# DriverBoardForCNC.net
KiCad netlist of a schematic drawn in Altium Designer
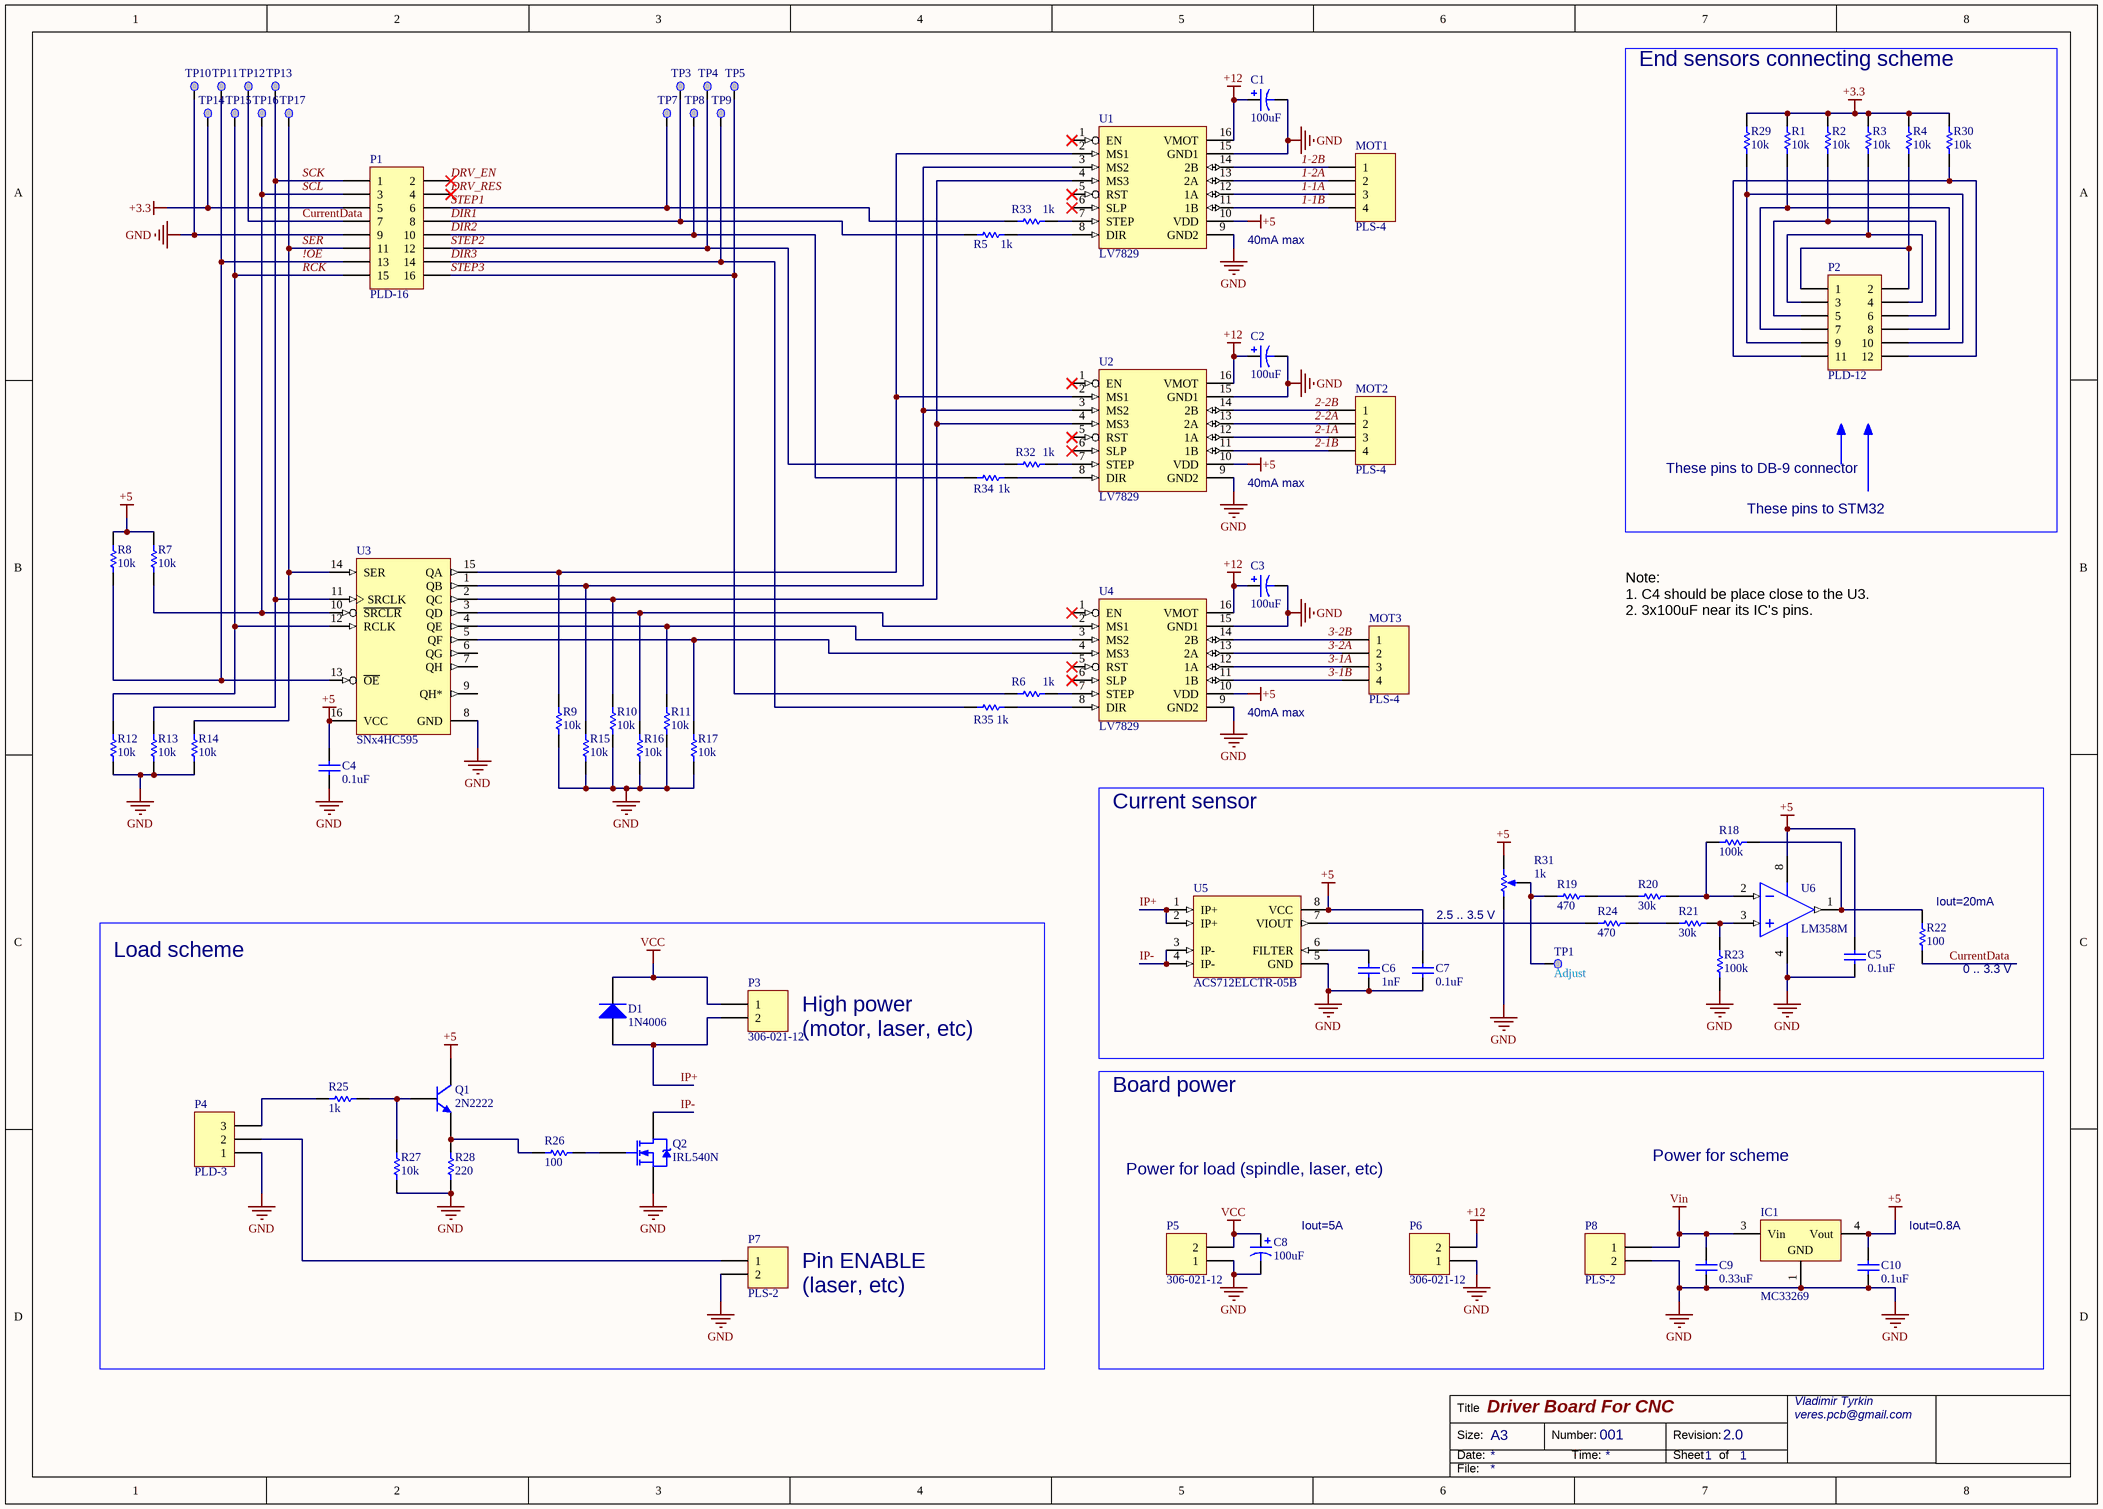
[diagram p0: DriverBoardForCNC.SchDoc]

(export (version "E")
  (design (tool "Eeschema 10.0.6"))
  (components
    (comp (ref "C1")
      (value "100uF")
      (footprint "UD-6,3X5,8_NICHICON")
      (description "Polarized Capacitor (Radial) 16V, 105°C, 20% 6.3x5.4mm")
      (fields (field (name "MANUFACTURER") "JB") (field (name "MANUFACTURER_PART_NUMBER") "JCL1C101M063054"))
      (libsource (lib "DriverBoardForCNC") (part "Cap Pol1"))
    )
    (comp (ref "C2")
      (value "100uF")
      (footprint "UD-6,3X5,8_NICHICON")
      (description "Polarized Capacitor (Radial) 16V, 105°C, 20% 6.3x5.4mm")
      (fields (field (name "MANUFACTURER") "JB") (field (name "MANUFACTURER_PART_NUMBER") "JCL1C101M063054"))
      (libsource (lib "DriverBoardForCNC") (part "Cap Pol1"))
    )
    (comp (ref "C3")
      (value "100uF")
      (footprint "UD-6,3X5,8_NICHICON")
      (description "Polarized Capacitor (Radial) 16V, 105°C, 20% 6.3x5.4mm")
      (fields (field (name "MANUFACTURER") "JB") (field (name "MANUFACTURER_PART_NUMBER") "JCL1C101M063054"))
      (libsource (lib "DriverBoardForCNC") (part "Cap Pol1"))
    )
    (comp (ref "C4")
      (value "0.1uF")
      (footprint "C1206")
      (description "Capacitor ceramic SMD")
      (fields
        (field (name "MANUFACTURER") "Murata")
        (field (name "MANUFACTURER_PART_NUMBER") "GRM319R71H104K")
      )
      (libsource (lib "DriverBoardForCNC") (part "Cap"))
    )
    (comp (ref "C5")
      (value "0.1uF")
      (footprint "C1206")
      (description "Capacitor ceramic SMD")
      (fields
        (field (name "MANUFACTURER") "Murata")
        (field (name "MANUFACTURER_PART_NUMBER") "GRM319R71H104K")
      )
      (libsource (lib "DriverBoardForCNC") (part "Cap"))
    )
    (comp (ref "C6")
      (value "1nF")
      (footprint "C0805")
      (description "Capacitor ceramic SMD")
      (fields
        (field (name "MANUFACTURER") "HOLYSTONECAPS")
        (field (name "MANUFACTURER_PART_NUMBER") "MLCC1000pFX7R50V10%0805")
      )
      (libsource (lib "DriverBoardForCNC") (part "Cap"))
    )
    (comp (ref "C7")
      (value "0.1uF")
      (footprint "C1206")
      (description "Capacitor ceramic SMD")
      (fields
        (field (name "MANUFACTURER") "Murata")
        (field (name "MANUFACTURER_PART_NUMBER") "GRM319R71H104K")
      )
      (libsource (lib "DriverBoardForCNC") (part "Cap"))
    )
    (comp (ref "C8")
      (value "100uF")
      (footprint "UD-6,3X5,8_NICHICON")
      (description "Polarized Capacitor (Radial) 16V, 105°C, 20% 6.3x5.4mm")
      (fields (field (name "MANUFACTURER") "JB") (field (name "MANUFACTURER_PART_NUMBER") "JCL1C101M063054"))
      (libsource (lib "DriverBoardForCNC") (part "Cap Pol1"))
    )
    (comp (ref "C9")
      (value "0.33uF")
      (footprint "C1206")
      (description "Capacitor ceramic SMD")
      (fields
        (field (name "MANUFACTURER") "Murata")
        (field (name "MANUFACTURER_PART_NUMBER") "GRM319R71H334KA01D")
      )
      (libsource (lib "DriverBoardForCNC") (part "Cap"))
    )
    (comp (ref "C10")
      (value "0.1uF")
      (footprint "C1206")
      (description "Capacitor ceramic SMD")
      (fields
        (field (name "MANUFACTURER") "Murata")
        (field (name "MANUFACTURER_PART_NUMBER") "GRM319R71H104K")
      )
      (libsource (lib "DriverBoardForCNC") (part "Cap"))
    )
    (comp (ref "D1")
      (value "1N4006")
      (footprint "DO-41")
      (description "1 Amp General Purpose Rectifier")
      (fields (field (name "MANUFACTURER") "DC COMPONENTS CO., LTD."))
      (libsource (lib "DriverBoardForCNC") (part "Diode 1N4004"))
    )
    (comp (ref "IC1")
      (value "MC33269")
      (footprint "DPAK")
      (description "5V Voltage Regulator")
      (fields
        (field (name "MANUFACTURER_PART_NUMBER") "MC33269DT−5.0")
        (field (name "MANUFACTURER") "ON Semiconductor")
      )
      (libsource (lib "DriverBoardForCNC") (part "Volt Reg 5V"))
    )
    (comp (ref "MOT1")
      (value "PLS-4")
      (footprint "HDR1X4")
      (description "Header, 4-Pin")
      (fields
        (field (name "MANUFACTURER") "Connfly")
        (field (name "MANUFACTURER_PART_NUMBER") "DS1021-1*4SF11-B")
      )
      (libsource (lib "DriverBoardForCNC") (part "Header 4"))
    )
    (comp (ref "MOT2")
      (value "PLS-4")
      (footprint "HDR1X4")
      (description "Header, 4-Pin")
      (fields
        (field (name "MANUFACTURER") "Connfly")
        (field (name "MANUFACTURER_PART_NUMBER") "DS1021-1*4SF11-B")
      )
      (libsource (lib "DriverBoardForCNC") (part "Header 4"))
    )
    (comp (ref "MOT3")
      (value "PLS-4")
      (footprint "HDR1X4")
      (description "Header, 4-Pin")
      (fields
        (field (name "MANUFACTURER") "Connfly")
        (field (name "MANUFACTURER_PART_NUMBER") "DS1021-1*4SF11-B")
      )
      (libsource (lib "DriverBoardForCNC") (part "Header 4"))
    )
    (comp (ref "P1")
      (value "PLD-16")
      (footprint "HDR2X8")
      (description "Header, 8-Pin, Dual row")
      (fields
        (field (name "MANUFACTURER") "Connfly")
        (field (name "MANUFACTURER_PART_NUMBER") "DS1021-2*8SF11-B")
      )
      (libsource (lib "DriverBoardForCNC") (part "Header 8X2"))
    )
    (comp (ref "P2")
      (value "PLD-12")
      (footprint "HDR2X6")
      (description "Header, 6-Pin, Dual row")
      (fields
        (field (name "MANUFACTURER") "Connfly")
        (field (name "MANUFACTURER_PART_NUMBER") "DS1021-2*6SF11-B")
      )
      (libsource (lib "DriverBoardForCNC") (part "Header 6X2"))
    )
    (comp (ref "P3")
      (value "306-021-12")
      (footprint "W237-102")
      (description "Screw connector, 2-Pin")
      (fields
        (field (name "MANUFACTURER") "Ningbo Xinya M&E")
        (field (name "MANUFACTURER_PART_NUMBER") "XY306A-5.0-2P-12")
      )
      (libsource (lib "") (part "Header 2_1"))
    )
    (comp (ref "P4")
      (value "PLD-3")
      (footprint "HDR1X3")
      (description "Header, 3-Pin")
      (fields
        (field (name "MANUFACTURER") "Connfly")
        (field (name "MANUFACTURER_PART_NUMBER") "DS1021-1*3SF11-B")
      )
      (libsource (lib "DriverBoardForCNC") (part "Header 3"))
    )
    (comp (ref "P5")
      (value "306-021-12")
      (footprint "W237-102")
      (description "Screw connector, 2-Pin")
      (fields
        (field (name "MANUFACTURER") "Ningbo Xinya M&E")
        (field (name "MANUFACTURER_PART_NUMBER") "XY306A-5.0-2P-12")
      )
      (libsource (lib "DriverBoardForCNC") (part "Header 2"))
    )
    (comp (ref "P6")
      (value "306-021-12")
      (footprint "W237-102")
      (description "Screw connector, 2-Pin")
      (fields
        (field (name "MANUFACTURER") "Ningbo Xinya M&E")
        (field (name "MANUFACTURER_PART_NUMBER") "XY306A-5.0-2P-12")
      )
      (libsource (lib "DriverBoardForCNC") (part "Header 2"))
    )
    (comp (ref "P7")
      (value "PLS-2")
      (footprint "HDR1X2")
      (description "Header, 2-Pin")
      (fields
        (field (name "MANUFACTURER") "Connfly")
        (field (name "MANUFACTURER_PART_NUMBER") "DS1021-1*2SF11-B")
      )
      (libsource (lib "") (part "Header 2_1"))
    )
    (comp (ref "P8")
      (value "PLS-2")
      (footprint "HDR1X2")
      (description "Header, 2-Pin")
      (fields
        (field (name "MANUFACTURER") "Connfly")
        (field (name "MANUFACTURER_PART_NUMBER") "DS1021-1*2SF11-B")
      )
      (libsource (lib "") (part "Header 2_2"))
    )
    (comp (ref "Q1")
      (value "2N2222")
      (footprint "TO92")
      (description "NPN Bipolar Transistor")
      (fields
        (field (name "MANUFACTURER") "ON Semiconductor")
        (field (name "MANUFACTURER_PART_NUMBER") "KSP2222ABU")
      )
      (libsource (lib "DriverBoardForCNC") (part "NPN"))
    )
    (comp (ref "Q2")
      (value "IRL540N")
      (footprint "TO220BV")
      (description "N-Channel Power MOSFET")
      (fields
        (field (name "MANUFACTURER") "Infineon Technologies")
        (field (name "MANUFACTURER_PART_NUMBER") "IRL540NPBF")
      )
      (libsource (lib "DriverBoardForCNC") (part "NMOS-2"))
    )
    (comp (ref "R1")
      (value "10k")
      (footprint "RES-0805")
      (description "Rectangular Thick Film Chip Resistor")
      (fields
        (field (name "MANUFACTURER_PART_NUMBER") "RC0805FR-0710KL")
        (field (name "MANUFACTURER") "Yageo")
      )
      (libsource (lib "DriverBoardForCNC") (part "Res"))
    )
    (comp (ref "R2")
      (value "10k")
      (footprint "RES-0805")
      (description "Rectangular Thick Film Chip Resistor")
      (fields
        (field (name "MANUFACTURER_PART_NUMBER") "RC0805FR-0710KL")
        (field (name "MANUFACTURER") "Yageo")
      )
      (libsource (lib "DriverBoardForCNC") (part "Res"))
    )
    (comp (ref "R3")
      (value "10k")
      (footprint "RES-0805")
      (description "Rectangular Thick Film Chip Resistor")
      (fields
        (field (name "MANUFACTURER_PART_NUMBER") "RC0805FR-0710KL")
        (field (name "MANUFACTURER") "Yageo")
      )
      (libsource (lib "DriverBoardForCNC") (part "Res"))
    )
    (comp (ref "R4")
      (value "10k")
      (footprint "RES-0805")
      (description "Rectangular Thick Film Chip Resistor")
      (fields
        (field (name "MANUFACTURER_PART_NUMBER") "RC0805FR-0710KL")
        (field (name "MANUFACTURER") "Yageo")
      )
      (libsource (lib "DriverBoardForCNC") (part "Res"))
    )
    (comp (ref "R5")
      (value "1k")
      (footprint "RES-0805")
      (description "Rectangular Thick Film Chip Resistor")
      (fields
        (field (name "MANUFACTURER") "Yageo")
        (field (name "MANUFACTURER_PART_NUMBER") "RC0805FR-071KL")
      )
      (libsource (lib "DriverBoardForCNC") (part "Res"))
    )
    (comp (ref "R6")
      (value "1k")
      (footprint "RES-0805")
      (description "Rectangular Thick Film Chip Resistor")
      (fields
        (field (name "MANUFACTURER") "Yageo")
        (field (name "MANUFACTURER_PART_NUMBER") "RC0805FR-071KL")
      )
      (libsource (lib "DriverBoardForCNC") (part "Res"))
    )
    (comp (ref "R7")
      (value "10k")
      (footprint "RES-0805")
      (description "Rectangular Thick Film Chip Resistor")
      (fields
        (field (name "MANUFACTURER_PART_NUMBER") "RC0805FR-0710KL")
        (field (name "MANUFACTURER") "Yageo")
      )
      (libsource (lib "DriverBoardForCNC") (part "Res"))
    )
    (comp (ref "R8")
      (value "10k")
      (footprint "RES-0805")
      (description "Rectangular Thick Film Chip Resistor")
      (fields
        (field (name "MANUFACTURER_PART_NUMBER") "RC0805FR-0710KL")
        (field (name "MANUFACTURER") "Yageo")
      )
      (libsource (lib "DriverBoardForCNC") (part "Res"))
    )
    (comp (ref "R9")
      (value "10k")
      (footprint "RES-0805")
      (description "Rectangular Thick Film Chip Resistor")
      (fields
        (field (name "MANUFACTURER_PART_NUMBER") "RC0805FR-0710KL")
        (field (name "MANUFACTURER") "Yageo")
      )
      (libsource (lib "DriverBoardForCNC") (part "Res"))
    )
    (comp (ref "R10")
      (value "10k")
      (footprint "RES-0805")
      (description "Rectangular Thick Film Chip Resistor")
      (fields
        (field (name "MANUFACTURER_PART_NUMBER") "RC0805FR-0710KL")
        (field (name "MANUFACTURER") "Yageo")
      )
      (libsource (lib "DriverBoardForCNC") (part "Res"))
    )
    (comp (ref "R11")
      (value "10k")
      (footprint "RES-0805")
      (description "Rectangular Thick Film Chip Resistor")
      (fields
        (field (name "MANUFACTURER_PART_NUMBER") "RC0805FR-0710KL")
        (field (name "MANUFACTURER") "Yageo")
      )
      (libsource (lib "DriverBoardForCNC") (part "Res"))
    )
    (comp (ref "R12")
      (value "10k")
      (footprint "RES-0805")
      (description "Rectangular Thick Film Chip Resistor")
      (fields
        (field (name "MANUFACTURER_PART_NUMBER") "RC0805FR-0710KL")
        (field (name "MANUFACTURER") "Yageo")
      )
      (libsource (lib "DriverBoardForCNC") (part "Res"))
    )
    (comp (ref "R13")
      (value "10k")
      (footprint "RES-0805")
      (description "Rectangular Thick Film Chip Resistor")
      (fields
        (field (name "MANUFACTURER_PART_NUMBER") "RC0805FR-0710KL")
        (field (name "MANUFACTURER") "Yageo")
      )
      (libsource (lib "DriverBoardForCNC") (part "Res"))
    )
    (comp (ref "R14")
      (value "10k")
      (footprint "RES-0805")
      (description "Rectangular Thick Film Chip Resistor")
      (fields
        (field (name "MANUFACTURER_PART_NUMBER") "RC0805FR-0710KL")
        (field (name "MANUFACTURER") "Yageo")
      )
      (libsource (lib "DriverBoardForCNC") (part "Res"))
    )
    (comp (ref "R15")
      (value "10k")
      (footprint "RES-0805")
      (description "Rectangular Thick Film Chip Resistor")
      (fields
        (field (name "MANUFACTURER_PART_NUMBER") "RC0805FR-0710KL")
        (field (name "MANUFACTURER") "Yageo")
      )
      (libsource (lib "DriverBoardForCNC") (part "Res"))
    )
    (comp (ref "R16")
      (value "10k")
      (footprint "RES-0805")
      (description "Rectangular Thick Film Chip Resistor")
      (fields
        (field (name "MANUFACTURER_PART_NUMBER") "RC0805FR-0710KL")
        (field (name "MANUFACTURER") "Yageo")
      )
      (libsource (lib "DriverBoardForCNC") (part "Res"))
    )
    (comp (ref "R17")
      (value "10k")
      (footprint "RES-0805")
      (description "Rectangular Thick Film Chip Resistor")
      (fields
        (field (name "MANUFACTURER_PART_NUMBER") "RC0805FR-0710KL")
        (field (name "MANUFACTURER") "Yageo")
      )
      (libsource (lib "DriverBoardForCNC") (part "Res"))
    )
    (comp (ref "R18")
      (value "100k")
      (footprint "RES-0805")
      (description "Rectangular Thick Film Chip Resistor")
      (fields
        (field (name "MANUFACTURER_PART_NUMBER") "RC0805FR-07100KL")
        (field (name "MANUFACTURER") "Yageo")
      )
      (libsource (lib "DriverBoardForCNC") (part "Res"))
    )
    (comp (ref "R19")
      (value "470")
      (footprint "RES-0805")
      (description "Rectangular Thick Film Chip Resistor")
      (fields
        (field (name "MANUFACTURER_PART_NUMBER") "RC0805FR-07470RL")
        (field (name "MANUFACTURER") "Yageo")
      )
      (libsource (lib "DriverBoardForCNC") (part "Res"))
    )
    (comp (ref "R20")
      (value "30k")
      (footprint "RES-0805")
      (description "Rectangular Thick Film Chip Resistor")
      (fields
        (field (name "MANUFACTURER_PART_NUMBER") "RC0805FR-0730KL")
        (field (name "MANUFACTURER") "Yageo")
      )
      (libsource (lib "DriverBoardForCNC") (part "Res"))
    )
    (comp (ref "R21")
      (value "30k")
      (footprint "RES-0805")
      (description "Rectangular Thick Film Chip Resistor")
      (fields
        (field (name "MANUFACTURER_PART_NUMBER") "RC0805FR-0730KL")
        (field (name "MANUFACTURER") "Yageo")
      )
      (libsource (lib "DriverBoardForCNC") (part "Res"))
    )
    (comp (ref "R22")
      (value "100")
      (footprint "RES-0805")
      (description "Rectangular Thick Film Chip Resistor")
      (fields
        (field (name "MANUFACTURER_PART_NUMBER") "RC0805FR-07100RL")
        (field (name "MANUFACTURER") "Yageo")
      )
      (libsource (lib "DriverBoardForCNC") (part "Res"))
    )
    (comp (ref "R23")
      (value "100k")
      (footprint "RES-0805")
      (description "Rectangular Thick Film Chip Resistor")
      (fields
        (field (name "MANUFACTURER_PART_NUMBER") "RC0805FR-07100KL")
        (field (name "MANUFACTURER") "Yageo")
      )
      (libsource (lib "DriverBoardForCNC") (part "Res"))
    )
    (comp (ref "R24")
      (value "470")
      (footprint "RES-1206")
      (description "Rectangular Thick Film Chip Resistor")
      (fields
        (field (name "MANUFACTURER_PART_NUMBER") "RC1206FR-07470RL")
        (field (name "MANUFACTURER") "Yageo")
      )
      (libsource (lib "DriverBoardForCNC") (part "Res"))
    )
    (comp (ref "R25")
      (value "1k")
      (footprint "RES-0805")
      (description "Rectangular Thick Film Chip Resistor")
      (fields
        (field (name "MANUFACTURER") "Yageo")
        (field (name "MANUFACTURER_PART_NUMBER") "RC0805FR-071KL")
      )
      (libsource (lib "DriverBoardForCNC") (part "Res"))
    )
    (comp (ref "R26")
      (value "100")
      (footprint "RES-0805")
      (description "Rectangular Thick Film Chip Resistor")
      (fields
        (field (name "MANUFACTURER_PART_NUMBER") "RC0805FR-07100RL")
        (field (name "MANUFACTURER") "Yageo")
      )
      (libsource (lib "DriverBoardForCNC") (part "Res"))
    )
    (comp (ref "R27")
      (value "10k")
      (footprint "RES-0805")
      (description "Rectangular Thick Film Chip Resistor")
      (fields
        (field (name "MANUFACTURER_PART_NUMBER") "RC0805FR-0710KL")
        (field (name "MANUFACTURER") "Yageo")
      )
      (libsource (lib "DriverBoardForCNC") (part "Res"))
    )
    (comp (ref "R28")
      (value "220")
      (footprint "RES-0805")
      (description "Rectangular Thick Film Chip Resistor")
      (fields
        (field (name "MANUFACTURER_PART_NUMBER") "RC0805FR-07220RL")
        (field (name "MANUFACTURER") "Yageo")
      )
      (libsource (lib "DriverBoardForCNC") (part "Res"))
    )
    (comp (ref "R29")
      (value "10k")
      (footprint "RES-0805")
      (description "Rectangular Thick Film Chip Resistor")
      (fields
        (field (name "MANUFACTURER_PART_NUMBER") "RC0805FR-0710KL")
        (field (name "MANUFACTURER") "Yageo")
      )
      (libsource (lib "DriverBoardForCNC") (part "Res"))
    )
    (comp (ref "R30")
      (value "10k")
      (footprint "RES-0805")
      (description "Rectangular Thick Film Chip Resistor")
      (fields
        (field (name "MANUFACTURER_PART_NUMBER") "RC0805FR-0710KL")
        (field (name "MANUFACTURER") "Yageo")
      )
      (libsource (lib "DriverBoardForCNC") (part "Res"))
    )
    (comp (ref "R31")
      (value "1k")
      (footprint "VR5")
      (description "Potentiometer")
      (fields
        (field (name "MANUFACTURER_PART_NUMBER") "3296W-1-102LF")
        (field (name "MANUFACTURER") "Bourns")
      )
      (libsource (lib "DriverBoardForCNC") (part "RPot"))
    )
    (comp (ref "R32")
      (value "1k")
      (footprint "RES-0805")
      (description "Rectangular Thick Film Chip Resistor")
      (fields
        (field (name "MANUFACTURER") "Yageo")
        (field (name "MANUFACTURER_PART_NUMBER") "RC0805FR-071KL")
      )
      (libsource (lib "DriverBoardForCNC") (part "Res"))
    )
    (comp (ref "R33")
      (value "1k")
      (footprint "RES-0805")
      (description "Rectangular Thick Film Chip Resistor")
      (fields
        (field (name "MANUFACTURER") "Yageo")
        (field (name "MANUFACTURER_PART_NUMBER") "RC0805FR-071KL")
      )
      (libsource (lib "DriverBoardForCNC") (part "Res"))
    )
    (comp (ref "R34")
      (value "1k")
      (footprint "RES-0805")
      (description "Rectangular Thick Film Chip Resistor")
      (fields
        (field (name "MANUFACTURER") "Yageo")
        (field (name "MANUFACTURER_PART_NUMBER") "RC0805FR-071KL")
      )
      (libsource (lib "DriverBoardForCNC") (part "Res"))
    )
    (comp (ref "R35")
      (value "1k")
      (footprint "RES-0805")
      (description "Rectangular Thick Film Chip Resistor")
      (fields
        (field (name "MANUFACTURER") "Yageo")
        (field (name "MANUFACTURER_PART_NUMBER") "RC0805FR-071KL")
      )
      (libsource (lib "DriverBoardForCNC") (part "Res"))
    )
    (comp (ref "TP1")
      (value "Adjust")
      (footprint "TestPoint")
      (description "Test Point")
      (fields (field (name "MANUFACTURER_PART_NUMBER") "n/a"))
      (libsource (lib "") (part "Test Point_1"))
    )
    (comp (ref "TP3")
      (value "~")
      (footprint "TP_SMD_1MM")
      (description "Test Point")
      (fields (field (name "MANUFACTURER_PART_NUMBER") "n/a"))
      (libsource (lib "DriverBoardForCNC") (part "Test Point"))
    )
    (comp (ref "TP4")
      (value "~")
      (footprint "TP_SMD_1MM")
      (description "Test Point")
      (fields (field (name "MANUFACTURER_PART_NUMBER") "n/a"))
      (libsource (lib "DriverBoardForCNC") (part "Test Point"))
    )
    (comp (ref "TP5")
      (value "~")
      (footprint "TP_SMD_1MM")
      (description "Test Point")
      (fields (field (name "MANUFACTURER_PART_NUMBER") "n/a"))
      (libsource (lib "DriverBoardForCNC") (part "Test Point"))
    )
    (comp (ref "TP7")
      (value "~")
      (footprint "TP_SMD_1MM")
      (description "Test Point")
      (fields (field (name "MANUFACTURER_PART_NUMBER") "n/a"))
      (libsource (lib "DriverBoardForCNC") (part "Test Point"))
    )
    (comp (ref "TP8")
      (value "~")
      (footprint "TP_SMD_1MM")
      (description "Test Point")
      (fields (field (name "MANUFACTURER_PART_NUMBER") "n/a"))
      (libsource (lib "DriverBoardForCNC") (part "Test Point"))
    )
    (comp (ref "TP9")
      (value "~")
      (footprint "TP_SMD_1MM")
      (description "Test Point")
      (fields (field (name "MANUFACTURER_PART_NUMBER") "n/a"))
      (libsource (lib "DriverBoardForCNC") (part "Test Point"))
    )
    (comp (ref "TP10")
      (value "~")
      (footprint "TP_SMD_1MM")
      (description "Test Point")
      (fields (field (name "MANUFACTURER_PART_NUMBER") "n/a"))
      (libsource (lib "DriverBoardForCNC") (part "Test Point"))
    )
    (comp (ref "TP11")
      (value "~")
      (footprint "TP_SMD_1MM")
      (description "Test Point")
      (fields (field (name "MANUFACTURER_PART_NUMBER") "n/a"))
      (libsource (lib "DriverBoardForCNC") (part "Test Point"))
    )
    (comp (ref "TP12")
      (value "~")
      (footprint "TP_SMD_1MM")
      (description "Test Point")
      (fields (field (name "MANUFACTURER_PART_NUMBER") "n/a"))
      (libsource (lib "DriverBoardForCNC") (part "Test Point"))
    )
    (comp (ref "TP13")
      (value "~")
      (footprint "TP_SMD_1MM")
      (description "Test Point")
      (fields (field (name "MANUFACTURER_PART_NUMBER") "n/a"))
      (libsource (lib "DriverBoardForCNC") (part "Test Point"))
    )
    (comp (ref "TP14")
      (value "~")
      (footprint "TP_SMD_1MM")
      (description "Test Point")
      (fields (field (name "MANUFACTURER_PART_NUMBER") "n/a"))
      (libsource (lib "DriverBoardForCNC") (part "Test Point"))
    )
    (comp (ref "TP15")
      (value "~")
      (footprint "TP_SMD_1MM")
      (description "Test Point")
      (fields (field (name "MANUFACTURER_PART_NUMBER") "n/a"))
      (libsource (lib "DriverBoardForCNC") (part "Test Point"))
    )
    (comp (ref "TP16")
      (value "~")
      (footprint "TP_SMD_1MM")
      (description "Test Point")
      (fields (field (name "MANUFACTURER_PART_NUMBER") "n/a"))
      (libsource (lib "DriverBoardForCNC") (part "Test Point"))
    )
    (comp (ref "TP17")
      (value "~")
      (footprint "TP_SMD_1MM")
      (description "Test Point")
      (fields (field (name "MANUFACTURER_PART_NUMBER") "n/a"))
      (libsource (lib "DriverBoardForCNC") (part "Test Point"))
    )
    (comp (ref "U1")
      (value "LV7829")
      (footprint "LV8729_BREAKOUT")
      (description "Stepper motor driver")
      (fields (field (name "MANUFACTURER_PART_NUMBER") "LV7829 Module") (field (name "MANUFACTURER") "China"))
      (libsource (lib "DriverBoardForCNC") (part "LV7829"))
    )
    (comp (ref "U2")
      (value "LV7829")
      (footprint "LV8729_BREAKOUT")
      (description "Stepper motor driver")
      (fields (field (name "MANUFACTURER_PART_NUMBER") "LV7829 Module") (field (name "MANUFACTURER") "China"))
      (libsource (lib "DriverBoardForCNC") (part "LV7829"))
    )
    (comp (ref "U3")
      (value "SNx4HC595")
      (footprint "SO16")
      (description "8-bit shift register with 3-state output register")
      (fields (field (name "MANUFACTURER_PART_NUMBER") "SN74HC595D") (field (name "MANUFACTURER") "TI"))
      (libsource (lib "DriverBoardForCNC") (part "SNx4HC595"))
    )
    (comp (ref "U4")
      (value "LV7829")
      (footprint "LV8729_BREAKOUT")
      (description "Stepper motor driver")
      (fields (field (name "MANUFACTURER_PART_NUMBER") "LV7829 Module") (field (name "MANUFACTURER") "China"))
      (libsource (lib "DriverBoardForCNC") (part "LV7829"))
    )
    (comp (ref "U5")
      (value "ACS712ELCTR-05B")
      (footprint "SO-8_L")
      (description "Hall-Effect-Based Linear Current Sensor +-5A")
      (fields (field (name "MANUFACTURER") "Allegro") (field (name "Comment") "Current Sensor"))
      (libsource (lib "DriverBoardForCNC") (part "ACS712ELCTR-05B"))
    )
    (comp (ref "U6")
      (value "LM358M")
      (footprint "SO-8_L")
      (description "FET Operational Amplifier")
      (fields (field (name "MANUFACTURER_PART_NUMBER") "LM358M/NOPB") (field (name "MANUFACTURER") "TI"))
      (libsource (lib "DriverBoardForCNC") (part "Op Amp"))
    )
  )
  (nets
    (net (code "1") (name "+3.3") (class "Default")
      (node (ref "P1") (pin "5") (pinfunction "5_5") (pintype "passive"))
      (node (ref "R1") (pin "1") (pinfunction "1_1") (pintype "passive"))
      (node (ref "R2") (pin "1") (pinfunction "1_1") (pintype "passive"))
      (node (ref "R29") (pin "1") (pinfunction "1_1") (pintype "passive"))
      (node (ref "R3") (pin "1") (pinfunction "1_1") (pintype "passive"))
      (node (ref "R30") (pin "1") (pinfunction "1_1") (pintype "passive"))
      (node (ref "R4") (pin "1") (pinfunction "1_1") (pintype "passive"))
      (node (ref "TP14") (pin "1") (pinfunction "1_1") (pintype "passive"))
    )
    (net (code "2") (name "+5") (class "Default")
      (node (ref "C10") (pin "2") (pinfunction "2_2") (pintype "passive"))
      (node (ref "C4") (pin "2") (pinfunction "2_2") (pintype "passive"))
      (node (ref "C5") (pin "1") (pinfunction "1_1") (pintype "passive"))
      (node (ref "C7") (pin "2") (pinfunction "2_2") (pintype "passive"))
      (node (ref "IC1") (pin "4") (pinfunction "Vout_4") (pintype "passive"))
      (node (ref "Q1") (pin "1") (pinfunction "C_1") (pintype "passive"))
      (node (ref "R31") (pin "3") (pinfunction "BOT_3") (pintype "passive"))
      (node (ref "R7") (pin "1") (pinfunction "1_1") (pintype "passive"))
      (node (ref "R8") (pin "1") (pinfunction "1_1") (pintype "passive"))
      (node (ref "U1") (pin "10") (pinfunction "VDD_10") (pintype "power_in"))
      (node (ref "U2") (pin "10") (pinfunction "VDD_10") (pintype "power_in"))
      (node (ref "U3") (pin "16") (pinfunction "VCC_16") (pintype "power_in"))
      (node (ref "U4") (pin "10") (pinfunction "VDD_10") (pintype "power_in"))
      (node (ref "U5") (pin "8") (pinfunction "VCC_8") (pintype "power_in"))
      (node (ref "U6") (pin "8") (pinfunction "V+_8") (pintype "power_in"))
    )
    (net (code "3") (name "+12") (class "Default")
      (node (ref "C1") (pin "1") (pinfunction "1_1") (pintype "passive"))
      (node (ref "C2") (pin "1") (pinfunction "1_1") (pintype "passive"))
      (node (ref "C3") (pin "1") (pinfunction "1_1") (pintype "passive"))
      (node (ref "P6") (pin "2") (pinfunction "2_2") (pintype "passive"))
      (node (ref "U1") (pin "16") (pinfunction "VMOT_16") (pintype "power_in"))
      (node (ref "U2") (pin "16") (pinfunction "VMOT_16") (pintype "power_in"))
      (node (ref "U4") (pin "16") (pinfunction "VMOT_16") (pintype "power_in"))
    )
    (net (code "4") (name "/!OE") (class "Default")
      (node (ref "P1") (pin "13") (pinfunction "13_13") (pintype "passive"))
      (node (ref "R8") (pin "2") (pinfunction "2_2") (pintype "passive"))
      (node (ref "TP11") (pin "1") (pinfunction "1_1") (pintype "passive"))
      (node (ref "U3") (pin "13") (pinfunction "~{OE}_13") (pintype "input"))
    )
    (net (code "5") (name "/1-1A") (class "Default")
      (node (ref "MOT1") (pin "3") (pinfunction "3_3") (pintype "passive"))
      (node (ref "U1") (pin "12") (pinfunction "1A_12") (pintype "bidirectional"))
    )
    (net (code "6") (name "/1-1B") (class "Default")
      (node (ref "MOT1") (pin "4") (pinfunction "4_4") (pintype "passive"))
      (node (ref "U1") (pin "11") (pinfunction "1B_11") (pintype "bidirectional"))
    )
    (net (code "7") (name "/1-2A") (class "Default")
      (node (ref "MOT1") (pin "2") (pinfunction "2_2") (pintype "passive"))
      (node (ref "U1") (pin "13") (pinfunction "2A_13") (pintype "bidirectional"))
    )
    (net (code "8") (name "/1-2B") (class "Default")
      (node (ref "MOT1") (pin "1") (pinfunction "1_1") (pintype "passive"))
      (node (ref "U1") (pin "14") (pinfunction "2B_14") (pintype "bidirectional"))
    )
    (net (code "9") (name "/2-1A") (class "Default")
      (node (ref "MOT2") (pin "3") (pinfunction "3_3") (pintype "passive"))
      (node (ref "U2") (pin "12") (pinfunction "1A_12") (pintype "bidirectional"))
    )
    (net (code "10") (name "/2-1B") (class "Default")
      (node (ref "MOT2") (pin "4") (pinfunction "4_4") (pintype "passive"))
      (node (ref "U2") (pin "11") (pinfunction "1B_11") (pintype "bidirectional"))
    )
    (net (code "11") (name "/2-2A") (class "Default")
      (node (ref "MOT2") (pin "2") (pinfunction "2_2") (pintype "passive"))
      (node (ref "U2") (pin "13") (pinfunction "2A_13") (pintype "bidirectional"))
    )
    (net (code "12") (name "/2-2B") (class "Default")
      (node (ref "MOT2") (pin "1") (pinfunction "1_1") (pintype "passive"))
      (node (ref "U2") (pin "14") (pinfunction "2B_14") (pintype "bidirectional"))
    )
    (net (code "13") (name "/3-1A") (class "Default")
      (node (ref "MOT3") (pin "3") (pinfunction "3_3") (pintype "passive"))
      (node (ref "U4") (pin "12") (pinfunction "1A_12") (pintype "bidirectional"))
    )
    (net (code "14") (name "/3-1B") (class "Default")
      (node (ref "MOT3") (pin "4") (pinfunction "4_4") (pintype "passive"))
      (node (ref "U4") (pin "11") (pinfunction "1B_11") (pintype "bidirectional"))
    )
    (net (code "15") (name "/3-2A") (class "Default")
      (node (ref "MOT3") (pin "2") (pinfunction "2_2") (pintype "passive"))
      (node (ref "U4") (pin "13") (pinfunction "2A_13") (pintype "bidirectional"))
    )
    (net (code "16") (name "/3-2B") (class "Default")
      (node (ref "MOT3") (pin "1") (pinfunction "1_1") (pintype "passive"))
      (node (ref "U4") (pin "14") (pinfunction "2B_14") (pintype "bidirectional"))
    )
    (net (code "17") (name "/CurrentData") (class "Default")
      (node (ref "P1") (pin "7") (pinfunction "7_7") (pintype "passive"))
      (node (ref "R22") (pin "2") (pinfunction "2_2") (pintype "passive"))
      (node (ref "TP12") (pin "1") (pinfunction "1_1") (pintype "passive"))
    )
    (net (code "18") (name "/DIR1") (class "Default")
      (node (ref "P1") (pin "8") (pinfunction "8_8") (pintype "passive"))
      (node (ref "R5") (pin "2") (pinfunction "2_2") (pintype "passive"))
      (node (ref "TP3") (pin "1") (pinfunction "1_1") (pintype "passive"))
    )
    (net (code "19") (name "/DIR2") (class "Default")
      (node (ref "P1") (pin "10") (pinfunction "10_10") (pintype "passive"))
      (node (ref "R34") (pin "2") (pinfunction "2_2") (pintype "passive"))
      (node (ref "TP8") (pin "1") (pinfunction "1_1") (pintype "passive"))
    )
    (net (code "20") (name "/DIR3") (class "Default")
      (node (ref "P1") (pin "14") (pinfunction "14_14") (pintype "passive"))
      (node (ref "R35") (pin "2") (pinfunction "2_2") (pintype "passive"))
      (node (ref "TP9") (pin "1") (pinfunction "1_1") (pintype "passive"))
    )
    (net (code "21") (name "/DRV_EN") (class "Default")
      (node (ref "P1") (pin "2") (pinfunction "2_2") (pintype "passive+no_connect"))
    )
    (net (code "22") (name "/DRV_RES") (class "Default")
      (node (ref "P1") (pin "4") (pinfunction "4_4") (pintype "passive+no_connect"))
    )
    (net (code "23") (name "/IP+") (class "Default")
      (node (ref "D1") (pin "1") (pinfunction "A_1") (pintype "passive"))
      (node (ref "P3") (pin "2") (pinfunction "2_2") (pintype "passive"))
      (node (ref "U5") (pin "1") (pinfunction "IP+_1") (pintype "input"))
      (node (ref "U5") (pin "2") (pinfunction "IP+_2") (pintype "input"))
    )
    (net (code "24") (name "/IP-") (class "Default")
      (node (ref "Q2") (pin "2") (pinfunction "D_2") (pintype "passive"))
      (node (ref "U5") (pin "3") (pinfunction "IP-_3") (pintype "input"))
      (node (ref "U5") (pin "4") (pinfunction "IP-_4") (pintype "input"))
    )
    (net (code "25") (name "/RCK") (class "Default")
      (node (ref "P1") (pin "15") (pinfunction "15_15") (pintype "passive"))
      (node (ref "R12") (pin "1") (pinfunction "1_1") (pintype "passive"))
      (node (ref "TP15") (pin "1") (pinfunction "1_1") (pintype "passive"))
      (node (ref "U3") (pin "12") (pinfunction "RCLK_12") (pintype "input"))
    )
    (net (code "26") (name "/SCK") (class "Default")
      (node (ref "P1") (pin "1") (pinfunction "1_1") (pintype "passive"))
      (node (ref "R13") (pin "1") (pinfunction "1_1") (pintype "passive"))
      (node (ref "TP13") (pin "1") (pinfunction "1_1") (pintype "passive"))
      (node (ref "U3") (pin "11") (pinfunction "SRCLK_11") (pintype "input"))
    )
    (net (code "27") (name "/SCL") (class "Default")
      (node (ref "P1") (pin "3") (pinfunction "3_3") (pintype "passive"))
      (node (ref "R7") (pin "2") (pinfunction "2_2") (pintype "passive"))
      (node (ref "TP16") (pin "1") (pinfunction "1_1") (pintype "passive"))
      (node (ref "U3") (pin "10") (pinfunction "~{SRCLR}_10") (pintype "input"))
    )
    (net (code "28") (name "/SER") (class "Default")
      (node (ref "P1") (pin "11") (pinfunction "11_11") (pintype "passive"))
      (node (ref "R14") (pin "1") (pinfunction "1_1") (pintype "passive"))
      (node (ref "TP17") (pin "1") (pinfunction "1_1") (pintype "passive"))
      (node (ref "U3") (pin "14") (pinfunction "SER_14") (pintype "input"))
    )
    (net (code "29") (name "/STEP1") (class "Default")
      (node (ref "P1") (pin "6") (pinfunction "6_6") (pintype "passive"))
      (node (ref "R33") (pin "2") (pinfunction "2_2") (pintype "passive"))
      (node (ref "TP7") (pin "1") (pinfunction "1_1") (pintype "passive"))
    )
    (net (code "30") (name "/STEP2") (class "Default")
      (node (ref "P1") (pin "12") (pinfunction "12_12") (pintype "passive"))
      (node (ref "R32") (pin "2") (pinfunction "2_2") (pintype "passive"))
      (node (ref "TP4") (pin "1") (pinfunction "1_1") (pintype "passive"))
    )
    (net (code "31") (name "/STEP3") (class "Default")
      (node (ref "P1") (pin "16") (pinfunction "16_16") (pintype "passive"))
      (node (ref "R6") (pin "2") (pinfunction "2_2") (pintype "passive"))
      (node (ref "TP5") (pin "1") (pinfunction "1_1") (pintype "passive"))
    )
    (net (code "32") (name "GND") (class "Default")
      (node (ref "C1") (pin "2") (pinfunction "2_2") (pintype "passive"))
      (node (ref "C10") (pin "1") (pinfunction "1_1") (pintype "passive"))
      (node (ref "C2") (pin "2") (pinfunction "2_2") (pintype "passive"))
      (node (ref "C3") (pin "2") (pinfunction "2_2") (pintype "passive"))
      (node (ref "C4") (pin "1") (pinfunction "1_1") (pintype "passive"))
      (node (ref "C5") (pin "2") (pinfunction "2_2") (pintype "passive"))
      (node (ref "C6") (pin "1") (pinfunction "1_1") (pintype "passive"))
      (node (ref "C7") (pin "1") (pinfunction "1_1") (pintype "passive"))
      (node (ref "C8") (pin "2") (pinfunction "2_2") (pintype "passive"))
      (node (ref "C9") (pin "1") (pinfunction "1_1") (pintype "passive"))
      (node (ref "IC1") (pin "1") (pinfunction "GND_1") (pintype "passive"))
      (node (ref "P1") (pin "9") (pinfunction "9_9") (pintype "passive"))
      (node (ref "P4") (pin "1") (pinfunction "1_1") (pintype "passive"))
      (node (ref "P5") (pin "1") (pinfunction "1_1") (pintype "passive"))
      (node (ref "P6") (pin "1") (pinfunction "1_1") (pintype "passive"))
      (node (ref "P7") (pin "2") (pinfunction "2_2") (pintype "passive"))
      (node (ref "P8") (pin "2") (pinfunction "2_2") (pintype "passive"))
      (node (ref "Q2") (pin "3") (pinfunction "S_3") (pintype "passive"))
      (node (ref "R10") (pin "2") (pinfunction "2_2") (pintype "passive"))
      (node (ref "R11") (pin "2") (pinfunction "2_2") (pintype "passive"))
      (node (ref "R12") (pin "2") (pinfunction "2_2") (pintype "passive"))
      (node (ref "R13") (pin "2") (pinfunction "2_2") (pintype "passive"))
      (node (ref "R14") (pin "2") (pinfunction "2_2") (pintype "passive"))
      (node (ref "R15") (pin "2") (pinfunction "2_2") (pintype "passive"))
      (node (ref "R16") (pin "2") (pinfunction "2_2") (pintype "passive"))
      (node (ref "R17") (pin "2") (pinfunction "2_2") (pintype "passive"))
      (node (ref "R23") (pin "2") (pinfunction "2_2") (pintype "passive"))
      (node (ref "R27") (pin "2") (pinfunction "2_2") (pintype "passive"))
      (node (ref "R28") (pin "2") (pinfunction "2_2") (pintype "passive"))
      (node (ref "R31") (pin "1") (pinfunction "TOP_1") (pintype "passive"))
      (node (ref "R9") (pin "2") (pinfunction "2_2") (pintype "passive"))
      (node (ref "TP10") (pin "1") (pinfunction "1_1") (pintype "passive"))
      (node (ref "U1") (pin "15") (pinfunction "GND1_15") (pintype "power_in"))
      (node (ref "U1") (pin "9") (pinfunction "GND2_9") (pintype "power_in"))
      (node (ref "U2") (pin "15") (pinfunction "GND1_15") (pintype "power_in"))
      (node (ref "U2") (pin "9") (pinfunction "GND2_9") (pintype "power_in"))
      (node (ref "U3") (pin "8") (pinfunction "GND_8") (pintype "power_in"))
      (node (ref "U4") (pin "15") (pinfunction "GND1_15") (pintype "power_in"))
      (node (ref "U4") (pin "9") (pinfunction "GND2_9") (pintype "power_in"))
      (node (ref "U5") (pin "5") (pinfunction "GND_5") (pintype "power_in"))
      (node (ref "U6") (pin "4") (pinfunction "V-_4") (pintype "power_in"))
    )
    (net (code "33") (name "Net-(P2-Pad1)") (class "Default")
      (node (ref "P2") (pin "1") (pinfunction "1_1") (pintype "passive"))
      (node (ref "P2") (pin "2") (pinfunction "2_2") (pintype "passive"))
      (node (ref "R4") (pin "2") (pinfunction "2_2") (pintype "passive"))
    )
    (net (code "34") (name "Net-(P2-Pad3)") (class "Default")
      (node (ref "P2") (pin "3") (pinfunction "3_3") (pintype "passive"))
      (node (ref "P2") (pin "4") (pinfunction "4_4") (pintype "passive"))
      (node (ref "R3") (pin "2") (pinfunction "2_2") (pintype "passive"))
    )
    (net (code "35") (name "Net-(P2-Pad5)") (class "Default")
      (node (ref "P2") (pin "5") (pinfunction "5_5") (pintype "passive"))
      (node (ref "P2") (pin "6") (pinfunction "6_6") (pintype "passive"))
      (node (ref "R2") (pin "2") (pinfunction "2_2") (pintype "passive"))
    )
    (net (code "36") (name "Net-(P2-Pad7)") (class "Default")
      (node (ref "P2") (pin "7") (pinfunction "7_7") (pintype "passive"))
      (node (ref "P2") (pin "8") (pinfunction "8_8") (pintype "passive"))
      (node (ref "R1") (pin "2") (pinfunction "2_2") (pintype "passive"))
    )
    (net (code "37") (name "Net-(P2-Pad10)") (class "Default")
      (node (ref "P2") (pin "10") (pinfunction "10_10") (pintype "passive"))
      (node (ref "P2") (pin "9") (pinfunction "9_9") (pintype "passive"))
      (node (ref "R29") (pin "2") (pinfunction "2_2") (pintype "passive"))
    )
    (net (code "38") (name "Net-(P2-Pad11)") (class "Default")
      (node (ref "P2") (pin "11") (pinfunction "11_11") (pintype "passive"))
      (node (ref "P2") (pin "12") (pinfunction "12_12") (pintype "passive"))
      (node (ref "R30") (pin "2") (pinfunction "2_2") (pintype "passive"))
    )
    (net (code "39") (name "Net-(P4-Pad2)") (class "Default")
      (node (ref "P4") (pin "2") (pinfunction "2_2") (pintype "passive"))
      (node (ref "P7") (pin "1") (pinfunction "1_1") (pintype "passive"))
    )
    (net (code "40") (name "Net-(P4-Pad3)") (class "Default")
      (node (ref "P4") (pin "3") (pinfunction "3_3") (pintype "passive"))
      (node (ref "R25") (pin "2") (pinfunction "2_2") (pintype "passive"))
    )
    (net (code "41") (name "Net-(Q1-B)") (class "Default")
      (node (ref "Q1") (pin "2") (pinfunction "B_2") (pintype "passive"))
      (node (ref "R25") (pin "1") (pinfunction "1_1") (pintype "passive"))
      (node (ref "R27") (pin "1") (pinfunction "1_1") (pintype "passive"))
    )
    (net (code "42") (name "Net-(Q1-E)") (class "Default")
      (node (ref "Q1") (pin "3") (pinfunction "E_3") (pintype "passive"))
      (node (ref "R26") (pin "2") (pinfunction "2_2") (pintype "passive"))
      (node (ref "R28") (pin "1") (pinfunction "1_1") (pintype "passive"))
    )
    (net (code "43") (name "Net-(Q2-G)") (class "Default")
      (node (ref "Q2") (pin "1") (pinfunction "G_1") (pintype "passive"))
      (node (ref "R26") (pin "1") (pinfunction "1_1") (pintype "passive"))
    )
    (net (code "44") (name "Net-(R19-Pad2)") (class "Default")
      (node (ref "R19") (pin "2") (pinfunction "2_2") (pintype "passive"))
      (node (ref "R20") (pin "2") (pinfunction "2_2") (pintype "passive"))
    )
    (net (code "45") (name "Net-(R21-Pad2)") (class "Default")
      (node (ref "R21") (pin "2") (pinfunction "2_2") (pintype "passive"))
      (node (ref "R24") (pin "2") (pinfunction "2_2") (pintype "passive"))
    )
    (net (code "46") (name "Net-(R31-TAP)") (class "Default")
      (node (ref "R19") (pin "1") (pinfunction "1_1") (pintype "passive"))
      (node (ref "R31") (pin "2") (pinfunction "TAP_2") (pintype "passive"))
      (node (ref "TP1") (pin "1") (pinfunction "1_1") (pintype "passive"))
    )
    (net (code "47") (name "Net-(U1-DIR)") (class "Default")
      (node (ref "R5") (pin "1") (pinfunction "1_1") (pintype "passive"))
      (node (ref "U1") (pin "8") (pinfunction "DIR_8") (pintype "input"))
    )
    (net (code "48") (name "Net-(U1-MS1)") (class "Default")
      (node (ref "R9") (pin "1") (pinfunction "1_1") (pintype "passive"))
      (node (ref "U1") (pin "2") (pinfunction "MS1_2") (pintype "input"))
      (node (ref "U2") (pin "2") (pinfunction "MS1_2") (pintype "input"))
      (node (ref "U3") (pin "15") (pinfunction "QA_15") (pintype "output"))
    )
    (net (code "49") (name "Net-(U1-MS2)") (class "Default")
      (node (ref "R15") (pin "1") (pinfunction "1_1") (pintype "passive"))
      (node (ref "U1") (pin "3") (pinfunction "MS2_3") (pintype "input"))
      (node (ref "U2") (pin "3") (pinfunction "MS2_3") (pintype "input"))
      (node (ref "U3") (pin "1") (pinfunction "QB_1") (pintype "output"))
    )
    (net (code "50") (name "Net-(U1-MS3)") (class "Default")
      (node (ref "R10") (pin "1") (pinfunction "1_1") (pintype "passive"))
      (node (ref "U1") (pin "4") (pinfunction "MS3_4") (pintype "input"))
      (node (ref "U2") (pin "4") (pinfunction "MS3_4") (pintype "input"))
      (node (ref "U3") (pin "2") (pinfunction "QC_2") (pintype "output"))
    )
    (net (code "51") (name "Net-(U1-STEP)") (class "Default")
      (node (ref "R33") (pin "1") (pinfunction "1_1") (pintype "passive"))
      (node (ref "U1") (pin "7") (pinfunction "STEP_7") (pintype "input"))
    )
    (net (code "52") (name "Net-(U2-DIR)") (class "Default")
      (node (ref "R34") (pin "1") (pinfunction "1_1") (pintype "passive"))
      (node (ref "U2") (pin "8") (pinfunction "DIR_8") (pintype "input"))
    )
    (net (code "53") (name "Net-(U2-STEP)") (class "Default")
      (node (ref "R32") (pin "1") (pinfunction "1_1") (pintype "passive"))
      (node (ref "U2") (pin "7") (pinfunction "STEP_7") (pintype "input"))
    )
    (net (code "54") (name "Net-(U3-QD)") (class "Default")
      (node (ref "R16") (pin "1") (pinfunction "1_1") (pintype "passive"))
      (node (ref "U3") (pin "3") (pinfunction "QD_3") (pintype "output"))
      (node (ref "U4") (pin "2") (pinfunction "MS1_2") (pintype "input"))
    )
    (net (code "55") (name "Net-(U3-QE)") (class "Default")
      (node (ref "R11") (pin "1") (pinfunction "1_1") (pintype "passive"))
      (node (ref "U3") (pin "4") (pinfunction "QE_4") (pintype "output"))
      (node (ref "U4") (pin "3") (pinfunction "MS2_3") (pintype "input"))
    )
    (net (code "56") (name "Net-(U3-QF)") (class "Default")
      (node (ref "R17") (pin "1") (pinfunction "1_1") (pintype "passive"))
      (node (ref "U3") (pin "5") (pinfunction "QF_5") (pintype "output"))
      (node (ref "U4") (pin "4") (pinfunction "MS3_4") (pintype "input"))
    )
    (net (code "57") (name "Net-(U4-DIR)") (class "Default")
      (node (ref "R35") (pin "1") (pinfunction "1_1") (pintype "passive"))
      (node (ref "U4") (pin "8") (pinfunction "DIR_8") (pintype "input"))
    )
    (net (code "58") (name "Net-(U4-STEP)") (class "Default")
      (node (ref "R6") (pin "1") (pinfunction "1_1") (pintype "passive"))
      (node (ref "U4") (pin "7") (pinfunction "STEP_7") (pintype "input"))
    )
    (net (code "59") (name "Net-(U5-FILTER)") (class "Default")
      (node (ref "C6") (pin "2") (pinfunction "2_2") (pintype "passive"))
      (node (ref "U5") (pin "6") (pinfunction "FILTER_6") (pintype "input"))
    )
    (net (code "60") (name "Net-(U5-VIOUT)") (class "Default")
      (node (ref "R24") (pin "1") (pinfunction "1_1") (pintype "passive"))
      (node (ref "U5") (pin "7") (pinfunction "VIOUT_7") (pintype "output"))
    )
    (net (code "61") (name "Net-(U6-IN+)") (class "Default")
      (node (ref "R21") (pin "1") (pinfunction "1_1") (pintype "passive"))
      (node (ref "R23") (pin "1") (pinfunction "1_1") (pintype "passive"))
      (node (ref "U6") (pin "3") (pinfunction "IN+_3") (pintype "input"))
    )
    (net (code "62") (name "Net-(U6-IN-)") (class "Default")
      (node (ref "R18") (pin "1") (pinfunction "1_1") (pintype "passive"))
      (node (ref "R20") (pin "1") (pinfunction "1_1") (pintype "passive"))
      (node (ref "U6") (pin "2") (pinfunction "IN-_2") (pintype "input"))
    )
    (net (code "63") (name "Net-(U6-OUT)") (class "Default")
      (node (ref "R18") (pin "2") (pinfunction "2_2") (pintype "passive"))
      (node (ref "R22") (pin "1") (pinfunction "1_1") (pintype "passive"))
      (node (ref "U6") (pin "1") (pinfunction "OUT_1") (pintype "output"))
    )
    (net (code "64") (name "VCC") (class "Default")
      (node (ref "C8") (pin "1") (pinfunction "1_1") (pintype "passive"))
      (node (ref "D1") (pin "2") (pinfunction "K_2") (pintype "passive"))
      (node (ref "P3") (pin "1") (pinfunction "1_1") (pintype "passive"))
      (node (ref "P5") (pin "2") (pinfunction "2_2") (pintype "passive"))
    )
    (net (code "65") (name "Vin") (class "Default")
      (node (ref "C9") (pin "2") (pinfunction "2_2") (pintype "passive"))
      (node (ref "IC1") (pin "3") (pinfunction "Vin_3") (pintype "passive"))
      (node (ref "P8") (pin "1") (pinfunction "1_1") (pintype "passive"))
    )
    (net (code "66") (name "unconnected-(U1-EN-Pad1)") (class "Default")
      (node (ref "U1") (pin "1") (pinfunction "EN_1") (pintype "input+no_connect"))
    )
    (net (code "67") (name "unconnected-(U1-RST-Pad5)") (class "Default")
      (node (ref "U1") (pin "5") (pinfunction "RST_5") (pintype "input+no_connect"))
    )
    (net (code "68") (name "unconnected-(U1-SLP-Pad6)") (class "Default")
      (node (ref "U1") (pin "6") (pinfunction "SLP_6") (pintype "input+no_connect"))
    )
    (net (code "69") (name "unconnected-(U2-EN-Pad1)") (class "Default")
      (node (ref "U2") (pin "1") (pinfunction "EN_1") (pintype "input+no_connect"))
    )
    (net (code "70") (name "unconnected-(U2-RST-Pad5)") (class "Default")
      (node (ref "U2") (pin "5") (pinfunction "RST_5") (pintype "input+no_connect"))
    )
    (net (code "71") (name "unconnected-(U2-SLP-Pad6)") (class "Default")
      (node (ref "U2") (pin "6") (pinfunction "SLP_6") (pintype "input+no_connect"))
    )
    (net (code "72") (name "unconnected-(U3-QG-Pad6)") (class "Default")
      (node (ref "U3") (pin "6") (pinfunction "QG_6") (pintype "output"))
    )
    (net (code "73") (name "unconnected-(U3-QH*-Pad9)") (class "Default")
      (node (ref "U3") (pin "9") (pinfunction "QH*_9") (pintype "output"))
    )
    (net (code "74") (name "unconnected-(U3-QH-Pad7)") (class "Default")
      (node (ref "U3") (pin "7") (pinfunction "QH_7") (pintype "output"))
    )
    (net (code "75") (name "unconnected-(U4-EN-Pad1)") (class "Default")
      (node (ref "U4") (pin "1") (pinfunction "EN_1") (pintype "input+no_connect"))
    )
    (net (code "76") (name "unconnected-(U4-RST-Pad5)") (class "Default")
      (node (ref "U4") (pin "5") (pinfunction "RST_5") (pintype "input+no_connect"))
    )
    (net (code "77") (name "unconnected-(U4-SLP-Pad6)") (class "Default")
      (node (ref "U4") (pin "6") (pinfunction "SLP_6") (pintype "input+no_connect"))
    )
  )
)
